# sma-amplifier.net
KiCad netlist of a schematic drawn in Altium Designer
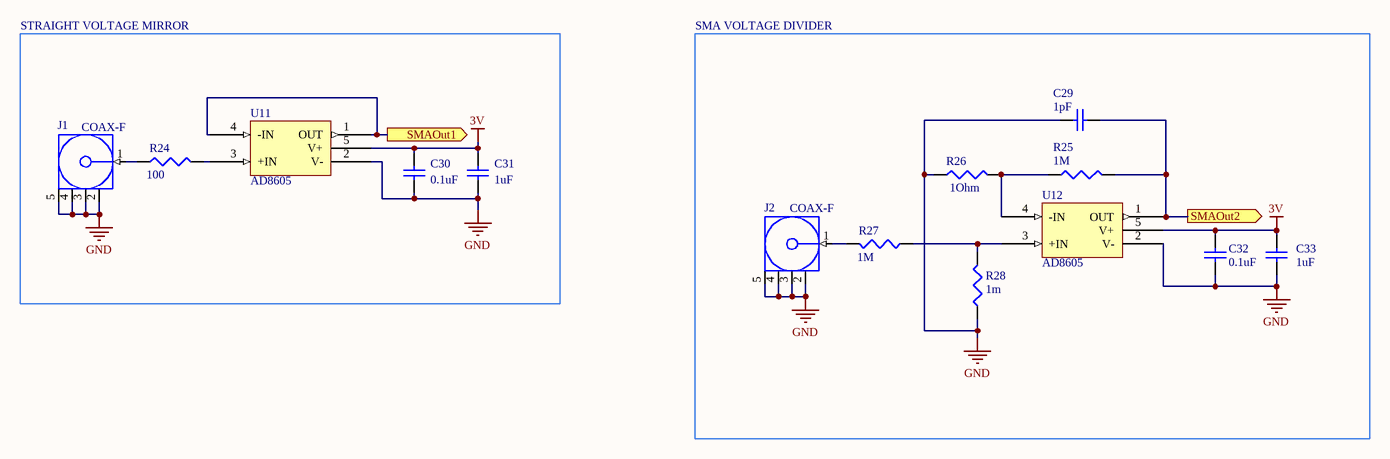
[diagram p0: sma-amplifier.SchDoc]

(export (version "E")
  (design (tool "Eeschema 10.0.6"))
  (components
    (comp (ref "C29")
      (value "1pF")
      (footprint "0402")
      (description "Capacitor (Semiconductor SIM Model)")
      (fields (field (name "PUBLISHER") "Altium Limited"))
      (libsource (lib "Miscellaneous Devices") (part "Cap Semi"))
    )
    (comp (ref "C30")
      (value "0.1uF")
      (footprint "0402")
      (description "Capacitor (Semiconductor SIM Model)")
      (fields (field (name "PUBLISHER") "Altium Limited"))
      (libsource (lib "Miscellaneous Devices") (part "Cap Semi"))
    )
    (comp (ref "C31")
      (value "1uF")
      (footprint "1608[0603]")
      (description "Capacitor (Semiconductor SIM Model)")
      (fields (field (name "PUBLISHER") "Altium Limited"))
      (libsource (lib "Miscellaneous Devices") (part "Cap Semi"))
    )
    (comp (ref "C32")
      (value "0.1uF")
      (footprint "0402")
      (description "Capacitor (Semiconductor SIM Model)")
      (fields (field (name "PUBLISHER") "Altium Limited"))
      (libsource (lib "Miscellaneous Devices") (part "Cap Semi"))
    )
    (comp (ref "C33")
      (value "1uF")
      (footprint "1608[0603]")
      (description "Capacitor (Semiconductor SIM Model)")
      (fields (field (name "PUBLISHER") "Altium Limited"))
      (libsource (lib "Miscellaneous Devices") (part "Cap Semi"))
    )
    (comp (ref "J1")
      (value "COAX-F")
      (footprint "MCX5.08-H5")
      (fields (field (name "PUBLISHER") "Altium Limited"))
      (libsource (lib "Miscellaneous Connectors") (part "COAX-F"))
    )
    (comp (ref "J2")
      (value "COAX-F")
      (footprint "MCX5.08-H5")
      (fields (field (name "PUBLISHER") "Altium Limited"))
      (libsource (lib "Miscellaneous Connectors") (part "COAX-F"))
    )
    (comp (ref "R24")
      (value "100")
      (footprint "0402")
      (description "Resistor")
      (fields (field (name "PUBLISHER") "Altium Limited"))
      (libsource (lib "Miscellaneous Devices") (part "Res3"))
    )
    (comp (ref "R25")
      (value "1M")
      (footprint "0402")
      (description "Resistor")
      (fields (field (name "PUBLISHER") "Altium Limited"))
      (libsource (lib "Miscellaneous Devices") (part "Res3"))
    )
    (comp (ref "R26")
      (value "1Ohm")
      (footprint "J1-0603")
      (description "Resistor")
      (fields (field (name "PUBLISHER") "Altium Limited"))
      (libsource (lib "Miscellaneous Devices") (part "Res3"))
    )
    (comp (ref "R27")
      (value "1M")
      (footprint "0402")
      (description "Resistor")
      (fields (field (name "PUBLISHER") "Altium Limited"))
      (libsource (lib "Miscellaneous Devices") (part "Res3"))
    )
    (comp (ref "R28")
      (value "1m")
      (footprint "14-1210")
      (description "Resistor")
      (fields (field (name "PUBLISHER") "Altium Limited"))
      (libsource (lib "Miscellaneous Devices") (part "Res3"))
    )
    (comp (ref "U11")
      (value "AD8605")
      (footprint "SOP-65P200X125-5N")
      (description "Low noise, precision rail-to-rail op-amp.")
      (libsource (lib "PAY") (part "AD8605"))
    )
    (comp (ref "U12")
      (value "AD8605")
      (footprint "SOP-65P200X125-5N")
      (description "Low noise, precision rail-to-rail op-amp.")
      (libsource (lib "PAY") (part "AD8605"))
    )
  )
  (nets
    (net (code "1") (name "/SMAOut1") (class "Default")
      (node (ref "U11") (pin "1") (pinfunction "OUT_1") (pintype "output"))
      (node (ref "U11") (pin "4") (pinfunction "-IN_4") (pintype "input"))
    )
    (net (code "2") (name "/SMAOut2") (class "Default")
      (node (ref "C29") (pin "1") (pinfunction "1_1") (pintype "passive"))
      (node (ref "R25") (pin "2") (pinfunction "2_2") (pintype "passive"))
      (node (ref "U12") (pin "1") (pinfunction "OUT_1") (pintype "output"))
    )
    (net (code "3") (name "3V") (class "Default")
      (node (ref "C30") (pin "2") (pinfunction "2_2") (pintype "passive"))
      (node (ref "C31") (pin "2") (pinfunction "2_2") (pintype "passive"))
      (node (ref "C32") (pin "2") (pinfunction "2_2") (pintype "passive"))
      (node (ref "C33") (pin "2") (pinfunction "2_2") (pintype "passive"))
      (node (ref "U11") (pin "5") (pinfunction "V+_5") (pintype "power_in"))
      (node (ref "U12") (pin "5") (pinfunction "V+_5") (pintype "power_in"))
    )
    (net (code "4") (name "GND") (class "Default")
      (node (ref "C29") (pin "2") (pinfunction "2_2") (pintype "passive"))
      (node (ref "C30") (pin "1") (pinfunction "1_1") (pintype "passive"))
      (node (ref "C31") (pin "1") (pinfunction "1_1") (pintype "passive"))
      (node (ref "C32") (pin "1") (pinfunction "1_1") (pintype "passive"))
      (node (ref "C33") (pin "1") (pinfunction "1_1") (pintype "passive"))
      (node (ref "J1") (pin "2") (pinfunction "GND_2") (pintype "power_in"))
      (node (ref "J1") (pin "3") (pinfunction "GND_3") (pintype "power_in"))
      (node (ref "J1") (pin "4") (pinfunction "GND_4") (pintype "power_in"))
      (node (ref "J1") (pin "5") (pinfunction "GND_5") (pintype "power_in"))
      (node (ref "J2") (pin "2") (pinfunction "GND_2") (pintype "power_in"))
      (node (ref "J2") (pin "3") (pinfunction "GND_3") (pintype "power_in"))
      (node (ref "J2") (pin "4") (pinfunction "GND_4") (pintype "power_in"))
      (node (ref "J2") (pin "5") (pinfunction "GND_5") (pintype "power_in"))
      (node (ref "R26") (pin "1") (pinfunction "1_1") (pintype "passive"))
      (node (ref "R28") (pin "1") (pinfunction "1_1") (pintype "passive"))
      (node (ref "U11") (pin "2") (pinfunction "V-_2") (pintype "power_in"))
      (node (ref "U12") (pin "2") (pinfunction "V-_2") (pintype "power_in"))
    )
    (net (code "5") (name "Net-(J1-Signal)") (class "Default")
      (node (ref "J1") (pin "1") (pinfunction "Signal_1") (pintype "input"))
      (node (ref "R24") (pin "1") (pinfunction "1_1") (pintype "passive"))
    )
    (net (code "6") (name "Net-(J2-Signal)") (class "Default")
      (node (ref "J2") (pin "1") (pinfunction "Signal_1") (pintype "input"))
      (node (ref "R27") (pin "2") (pinfunction "2_2") (pintype "passive"))
    )
    (net (code "7") (name "Net-(U11-+IN)") (class "Default")
      (node (ref "R24") (pin "2") (pinfunction "2_2") (pintype "passive"))
      (node (ref "U11") (pin "3") (pinfunction "+IN_3") (pintype "input"))
    )
    (net (code "8") (name "Net-(U12-+IN)") (class "Default")
      (node (ref "R27") (pin "1") (pinfunction "1_1") (pintype "passive"))
      (node (ref "R28") (pin "2") (pinfunction "2_2") (pintype "passive"))
      (node (ref "U12") (pin "3") (pinfunction "+IN_3") (pintype "input"))
    )
    (net (code "9") (name "Net-(U12--IN)") (class "Default")
      (node (ref "R25") (pin "1") (pinfunction "1_1") (pintype "passive"))
      (node (ref "R26") (pin "2") (pinfunction "2_2") (pintype "passive"))
      (node (ref "U12") (pin "4") (pinfunction "-IN_4") (pintype "input"))
    )
  )
)
